# H-bridge_double.net
KiCad netlist of a schematic drawn in EAGLE
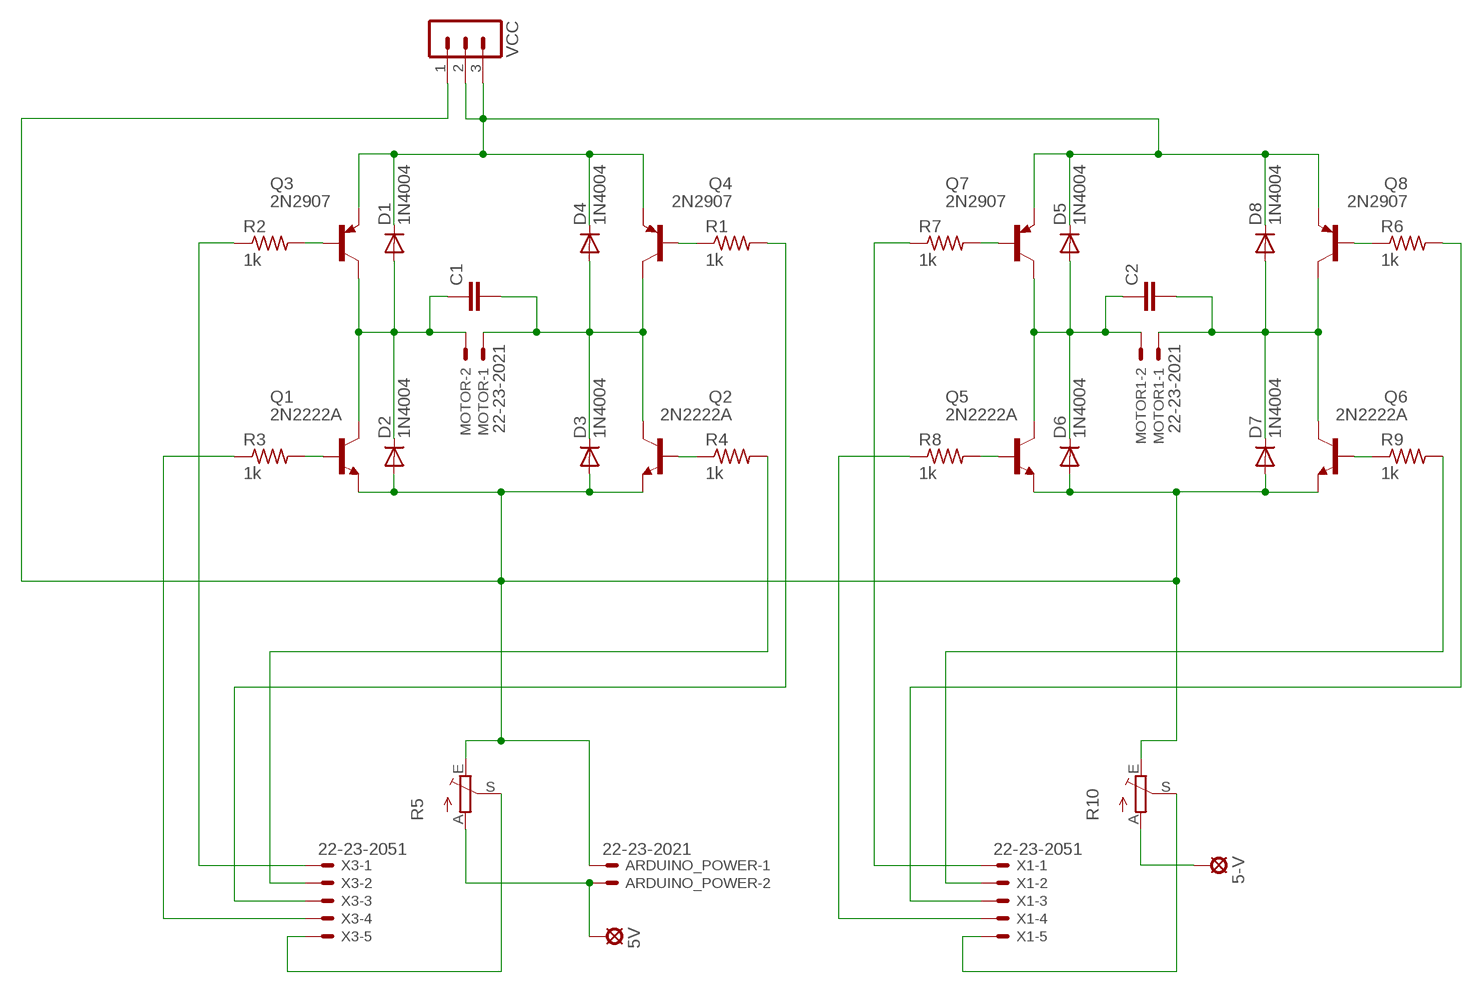
[diagram p0: schematic, sheet 1]

(export (version "E")
  (design (tool "Eeschema 10.0.6"))
  (components
    (comp (ref "5-V")
      (value "LSP10")
      (footprint "eagle-import:LSP10")
      (libsource (lib "eagle-import") (part "LSP10"))
    )
    (comp (ref "5V")
      (value "LSP10")
      (footprint "eagle-import:LSP10")
      (libsource (lib "eagle-import") (part "LSP10"))
    )
    (comp (ref "ARDUINO_POWER")
      (value "22-23-2021")
      (footprint "eagle-import:22-23-2021")
      (fields (field (name "MF") "MOLEX"))
      (libsource (lib "eagle-import") (part "22-23-2021"))
    )
    (comp (ref "C1")
      (value "C2.5/2")
      (footprint "eagle-import:C2.5-2")
      (libsource (lib "eagle-import") (part "C2.5/2"))
    )
    (comp (ref "C2")
      (value "C2.5/2")
      (footprint "eagle-import:C2.5-2")
      (libsource (lib "eagle-import") (part "C2.5/2"))
    )
    (comp (ref "D1")
      (value "1N4004")
      (footprint "eagle-import:DO41-10")
      (libsource (lib "eagle-import") (part "1N4004"))
    )
    (comp (ref "D2")
      (value "1N4004")
      (footprint "eagle-import:DO41-10")
      (libsource (lib "eagle-import") (part "1N4004"))
    )
    (comp (ref "D3")
      (value "1N4004")
      (footprint "eagle-import:DO41-10")
      (libsource (lib "eagle-import") (part "1N4004"))
    )
    (comp (ref "D4")
      (value "1N4004")
      (footprint "eagle-import:DO41-10")
      (libsource (lib "eagle-import") (part "1N4004"))
    )
    (comp (ref "D5")
      (value "1N4004")
      (footprint "eagle-import:DO41-10")
      (libsource (lib "eagle-import") (part "1N4004"))
    )
    (comp (ref "D6")
      (value "1N4004")
      (footprint "eagle-import:DO41-10")
      (libsource (lib "eagle-import") (part "1N4004"))
    )
    (comp (ref "D7")
      (value "1N4004")
      (footprint "eagle-import:DO41-10")
      (libsource (lib "eagle-import") (part "1N4004"))
    )
    (comp (ref "D8")
      (value "1N4004")
      (footprint "eagle-import:DO41-10")
      (libsource (lib "eagle-import") (part "1N4004"))
    )
    (comp (ref "MOTOR")
      (value "22-23-2021")
      (footprint "eagle-import:22-23-2021")
      (fields (field (name "MF") "MOLEX"))
      (libsource (lib "eagle-import") (part "22-23-2021"))
    )
    (comp (ref "MOTOR1")
      (value "22-23-2021")
      (footprint "eagle-import:22-23-2021")
      (fields (field (name "MF") "MOLEX"))
      (libsource (lib "eagle-import") (part "22-23-2021"))
    )
    (comp (ref "Q1")
      (value "2N2222A")
      (footprint "eagle-import:TO18")
      (libsource (lib "eagle-import") (part "2N2222A"))
    )
    (comp (ref "Q2")
      (value "2N2222A")
      (footprint "eagle-import:TO18")
      (libsource (lib "eagle-import") (part "2N2222A"))
    )
    (comp (ref "Q3")
      (value "2N2907")
      (footprint "eagle-import:TO18")
      (libsource (lib "eagle-import") (part "2N2907"))
    )
    (comp (ref "Q4")
      (value "2N2907")
      (footprint "eagle-import:TO18")
      (libsource (lib "eagle-import") (part "2N2907"))
    )
    (comp (ref "Q5")
      (value "2N2222A")
      (footprint "eagle-import:TO18")
      (libsource (lib "eagle-import") (part "2N2222A"))
    )
    (comp (ref "Q6")
      (value "2N2222A")
      (footprint "eagle-import:TO18")
      (libsource (lib "eagle-import") (part "2N2222A"))
    )
    (comp (ref "Q7")
      (value "2N2907")
      (footprint "eagle-import:TO18")
      (libsource (lib "eagle-import") (part "2N2907"))
    )
    (comp (ref "Q8")
      (value "2N2907")
      (footprint "eagle-import:TO18")
      (libsource (lib "eagle-import") (part "2N2907"))
    )
    (comp (ref "R1")
      (value "1k")
      (footprint "eagle-import:0309_12")
      (libsource (lib "eagle-import") (part "R-US_0309/12"))
    )
    (comp (ref "R2")
      (value "1k")
      (footprint "eagle-import:0309_12")
      (libsource (lib "eagle-import") (part "R-US_0309/12"))
    )
    (comp (ref "R3")
      (value "1k")
      (footprint "eagle-import:0309_12")
      (libsource (lib "eagle-import") (part "R-US_0309/12"))
    )
    (comp (ref "R4")
      (value "1k")
      (footprint "eagle-import:0309_12")
      (libsource (lib "eagle-import") (part "R-US_0309/12"))
    )
    (comp (ref "R5")
      (value "TRIM_EU-CA6V")
      (footprint "eagle-import:CA6V")
      (libsource (lib "eagle-import") (part "TRIM_EU-CA6V"))
    )
    (comp (ref "R6")
      (value "1k")
      (footprint "eagle-import:0309_12")
      (libsource (lib "eagle-import") (part "R-US_0309/12"))
    )
    (comp (ref "R7")
      (value "1k")
      (footprint "eagle-import:0309_12")
      (libsource (lib "eagle-import") (part "R-US_0309/12"))
    )
    (comp (ref "R8")
      (value "1k")
      (footprint "eagle-import:0309_12")
      (libsource (lib "eagle-import") (part "R-US_0309/12"))
    )
    (comp (ref "R9")
      (value "1k")
      (footprint "eagle-import:0309_12")
      (libsource (lib "eagle-import") (part "R-US_0309/12"))
    )
    (comp (ref "R10")
      (value "TRIM_EU-CA6V")
      (footprint "eagle-import:CA6V")
      (libsource (lib "eagle-import") (part "TRIM_EU-CA6V"))
    )
    (comp (ref "VCC")
      (value "MA03-1")
      (footprint "eagle-import:MA03-1")
      (libsource (lib "eagle-import") (part "MA03-1"))
    )
    (comp (ref "X1")
      (value "22-23-2051")
      (footprint "eagle-import:22-23-2051")
      (fields (field (name "MF") "MOLEX"))
      (libsource (lib "eagle-import") (part "22-23-2051"))
    )
    (comp (ref "X3")
      (value "22-23-2051")
      (footprint "eagle-import:22-23-2051")
      (fields (field (name "MF") "MOLEX"))
      (libsource (lib "eagle-import") (part "22-23-2051"))
    )
  )
  (nets
    (net (code "1") (name "Net-(5-V-PadMP)") (class "Default")
      (node (ref "5-V") (pin "MP") (pinfunction "MP_MP") (pintype "passive"))
      (node (ref "R10") (pin "A") (pinfunction "A_A") (pintype "passive"))
    )
    (net (code "2") (name "Net-(ARDUINO_POWERA-S)") (class "Default")
      (node (ref "ARDUINO_POWER") (pin "1") (pinfunction "S_1") (pintype "passive"))
      (node (ref "D2") (pin "A") (pinfunction "A_A") (pintype "passive"))
      (node (ref "D3") (pin "A") (pinfunction "A_A") (pintype "passive"))
      (node (ref "D6") (pin "A") (pinfunction "A_A") (pintype "passive"))
      (node (ref "D7") (pin "A") (pinfunction "A_A") (pintype "passive"))
      (node (ref "Q1") (pin "1") (pinfunction "E_1") (pintype "passive"))
      (node (ref "Q2") (pin "1") (pinfunction "E_1") (pintype "passive"))
      (node (ref "Q5") (pin "1") (pinfunction "E_1") (pintype "passive"))
      (node (ref "Q6") (pin "1") (pinfunction "E_1") (pintype "passive"))
      (node (ref "R10") (pin "E") (pinfunction "E_E") (pintype "passive"))
      (node (ref "R5") (pin "E") (pinfunction "E_E") (pintype "passive"))
      (node (ref "VCC") (pin "1") (pinfunction "1_1") (pintype "passive"))
    )
    (net (code "3") (name "Net-(ARDUINO_POWERB-S)") (class "Default")
      (node (ref "5V") (pin "MP") (pinfunction "MP_MP") (pintype "passive"))
      (node (ref "ARDUINO_POWER") (pin "2") (pinfunction "S_2") (pintype "passive"))
      (node (ref "R5") (pin "A") (pinfunction "A_A") (pintype "passive"))
    )
    (net (code "4") (name "Net-(MOTOR1A-S)") (class "Default")
      (node (ref "C2") (pin "2") (pinfunction "2_2") (pintype "passive"))
      (node (ref "D7") (pin "C") (pinfunction "C_C") (pintype "passive"))
      (node (ref "D8") (pin "A") (pinfunction "A_A") (pintype "passive"))
      (node (ref "MOTOR1") (pin "1") (pinfunction "S_1") (pintype "passive"))
      (node (ref "Q6") (pin "3") (pinfunction "C_3") (pintype "passive"))
      (node (ref "Q8") (pin "3") (pinfunction "C_3") (pintype "passive"))
    )
    (net (code "5") (name "Net-(MOTOR1B-S)") (class "Default")
      (node (ref "C2") (pin "1") (pinfunction "1_1") (pintype "passive"))
      (node (ref "D5") (pin "A") (pinfunction "A_A") (pintype "passive"))
      (node (ref "D6") (pin "C") (pinfunction "C_C") (pintype "passive"))
      (node (ref "MOTOR1") (pin "2") (pinfunction "S_2") (pintype "passive"))
      (node (ref "Q5") (pin "3") (pinfunction "C_3") (pintype "passive"))
      (node (ref "Q7") (pin "3") (pinfunction "C_3") (pintype "passive"))
    )
    (net (code "6") (name "Net-(MOTORA-S)") (class "Default")
      (node (ref "C1") (pin "2") (pinfunction "2_2") (pintype "passive"))
      (node (ref "D3") (pin "C") (pinfunction "C_C") (pintype "passive"))
      (node (ref "D4") (pin "A") (pinfunction "A_A") (pintype "passive"))
      (node (ref "MOTOR") (pin "1") (pinfunction "S_1") (pintype "passive"))
      (node (ref "Q2") (pin "3") (pinfunction "C_3") (pintype "passive"))
      (node (ref "Q4") (pin "3") (pinfunction "C_3") (pintype "passive"))
    )
    (net (code "7") (name "Net-(MOTORB-S)") (class "Default")
      (node (ref "C1") (pin "1") (pinfunction "1_1") (pintype "passive"))
      (node (ref "D1") (pin "A") (pinfunction "A_A") (pintype "passive"))
      (node (ref "D2") (pin "C") (pinfunction "C_C") (pintype "passive"))
      (node (ref "MOTOR") (pin "2") (pinfunction "S_2") (pintype "passive"))
      (node (ref "Q1") (pin "3") (pinfunction "C_3") (pintype "passive"))
      (node (ref "Q3") (pin "3") (pinfunction "C_3") (pintype "passive"))
    )
    (net (code "8") (name "Net-(Q1-B)") (class "Default")
      (node (ref "Q1") (pin "2") (pinfunction "B_2") (pintype "passive"))
      (node (ref "R3") (pin "2") (pinfunction "2_2") (pintype "passive"))
    )
    (net (code "9") (name "Net-(Q2-B)") (class "Default")
      (node (ref "Q2") (pin "2") (pinfunction "B_2") (pintype "passive"))
      (node (ref "R4") (pin "1") (pinfunction "1_1") (pintype "passive"))
    )
    (net (code "10") (name "Net-(Q3-B)") (class "Default")
      (node (ref "Q3") (pin "2") (pinfunction "B_2") (pintype "passive"))
      (node (ref "R2") (pin "2") (pinfunction "2_2") (pintype "passive"))
    )
    (net (code "11") (name "Net-(Q3-E)") (class "Default")
      (node (ref "D1") (pin "C") (pinfunction "C_C") (pintype "passive"))
      (node (ref "D4") (pin "C") (pinfunction "C_C") (pintype "passive"))
      (node (ref "D5") (pin "C") (pinfunction "C_C") (pintype "passive"))
      (node (ref "D8") (pin "C") (pinfunction "C_C") (pintype "passive"))
      (node (ref "Q3") (pin "1") (pinfunction "E_1") (pintype "passive"))
      (node (ref "Q4") (pin "1") (pinfunction "E_1") (pintype "passive"))
      (node (ref "Q7") (pin "1") (pinfunction "E_1") (pintype "passive"))
      (node (ref "Q8") (pin "1") (pinfunction "E_1") (pintype "passive"))
      (node (ref "VCC") (pin "2") (pinfunction "2_2") (pintype "passive"))
      (node (ref "VCC") (pin "3") (pinfunction "3_3") (pintype "passive"))
    )
    (net (code "12") (name "Net-(Q4-B)") (class "Default")
      (node (ref "Q4") (pin "2") (pinfunction "B_2") (pintype "passive"))
      (node (ref "R1") (pin "1") (pinfunction "1_1") (pintype "passive"))
    )
    (net (code "13") (name "Net-(Q5-B)") (class "Default")
      (node (ref "Q5") (pin "2") (pinfunction "B_2") (pintype "passive"))
      (node (ref "R8") (pin "2") (pinfunction "2_2") (pintype "passive"))
    )
    (net (code "14") (name "Net-(Q6-B)") (class "Default")
      (node (ref "Q6") (pin "2") (pinfunction "B_2") (pintype "passive"))
      (node (ref "R9") (pin "1") (pinfunction "1_1") (pintype "passive"))
    )
    (net (code "15") (name "Net-(Q7-B)") (class "Default")
      (node (ref "Q7") (pin "2") (pinfunction "B_2") (pintype "passive"))
      (node (ref "R7") (pin "2") (pinfunction "2_2") (pintype "passive"))
    )
    (net (code "16") (name "Net-(Q8-B)") (class "Default")
      (node (ref "Q8") (pin "2") (pinfunction "B_2") (pintype "passive"))
      (node (ref "R6") (pin "1") (pinfunction "1_1") (pintype "passive"))
    )
    (net (code "17") (name "Net-(X1A-S)") (class "Default")
      (node (ref "R7") (pin "1") (pinfunction "1_1") (pintype "passive"))
      (node (ref "X1") (pin "1") (pinfunction "S_1") (pintype "passive"))
    )
    (net (code "18") (name "Net-(X1B-S)") (class "Default")
      (node (ref "R9") (pin "2") (pinfunction "2_2") (pintype "passive"))
      (node (ref "X1") (pin "2") (pinfunction "S_2") (pintype "passive"))
    )
    (net (code "19") (name "Net-(X1C-S)") (class "Default")
      (node (ref "R6") (pin "2") (pinfunction "2_2") (pintype "passive"))
      (node (ref "X1") (pin "3") (pinfunction "S_3") (pintype "passive"))
    )
    (net (code "20") (name "Net-(X1D-S)") (class "Default")
      (node (ref "R8") (pin "1") (pinfunction "1_1") (pintype "passive"))
      (node (ref "X1") (pin "4") (pinfunction "S_4") (pintype "passive"))
    )
    (net (code "21") (name "Net-(X1E-S)") (class "Default")
      (node (ref "R10") (pin "S") (pinfunction "S_S") (pintype "passive"))
      (node (ref "X1") (pin "5") (pinfunction "S_5") (pintype "passive"))
    )
    (net (code "22") (name "Net-(X3A-S)") (class "Default")
      (node (ref "R2") (pin "1") (pinfunction "1_1") (pintype "passive"))
      (node (ref "X3") (pin "1") (pinfunction "S_1") (pintype "passive"))
    )
    (net (code "23") (name "Net-(X3B-S)") (class "Default")
      (node (ref "R4") (pin "2") (pinfunction "2_2") (pintype "passive"))
      (node (ref "X3") (pin "2") (pinfunction "S_2") (pintype "passive"))
    )
    (net (code "24") (name "Net-(X3C-S)") (class "Default")
      (node (ref "R1") (pin "2") (pinfunction "2_2") (pintype "passive"))
      (node (ref "X3") (pin "3") (pinfunction "S_3") (pintype "passive"))
    )
    (net (code "25") (name "Net-(X3D-S)") (class "Default")
      (node (ref "R3") (pin "1") (pinfunction "1_1") (pintype "passive"))
      (node (ref "X3") (pin "4") (pinfunction "S_4") (pintype "passive"))
    )
    (net (code "26") (name "Net-(X3E-S)") (class "Default")
      (node (ref "R5") (pin "S") (pinfunction "S_S") (pintype "passive"))
      (node (ref "X3") (pin "5") (pinfunction "S_5") (pintype "passive"))
    )
  )
)
